# VIC-20_AV-Adaptor.net
KiCad netlist of a schematic drawn in EAGLE
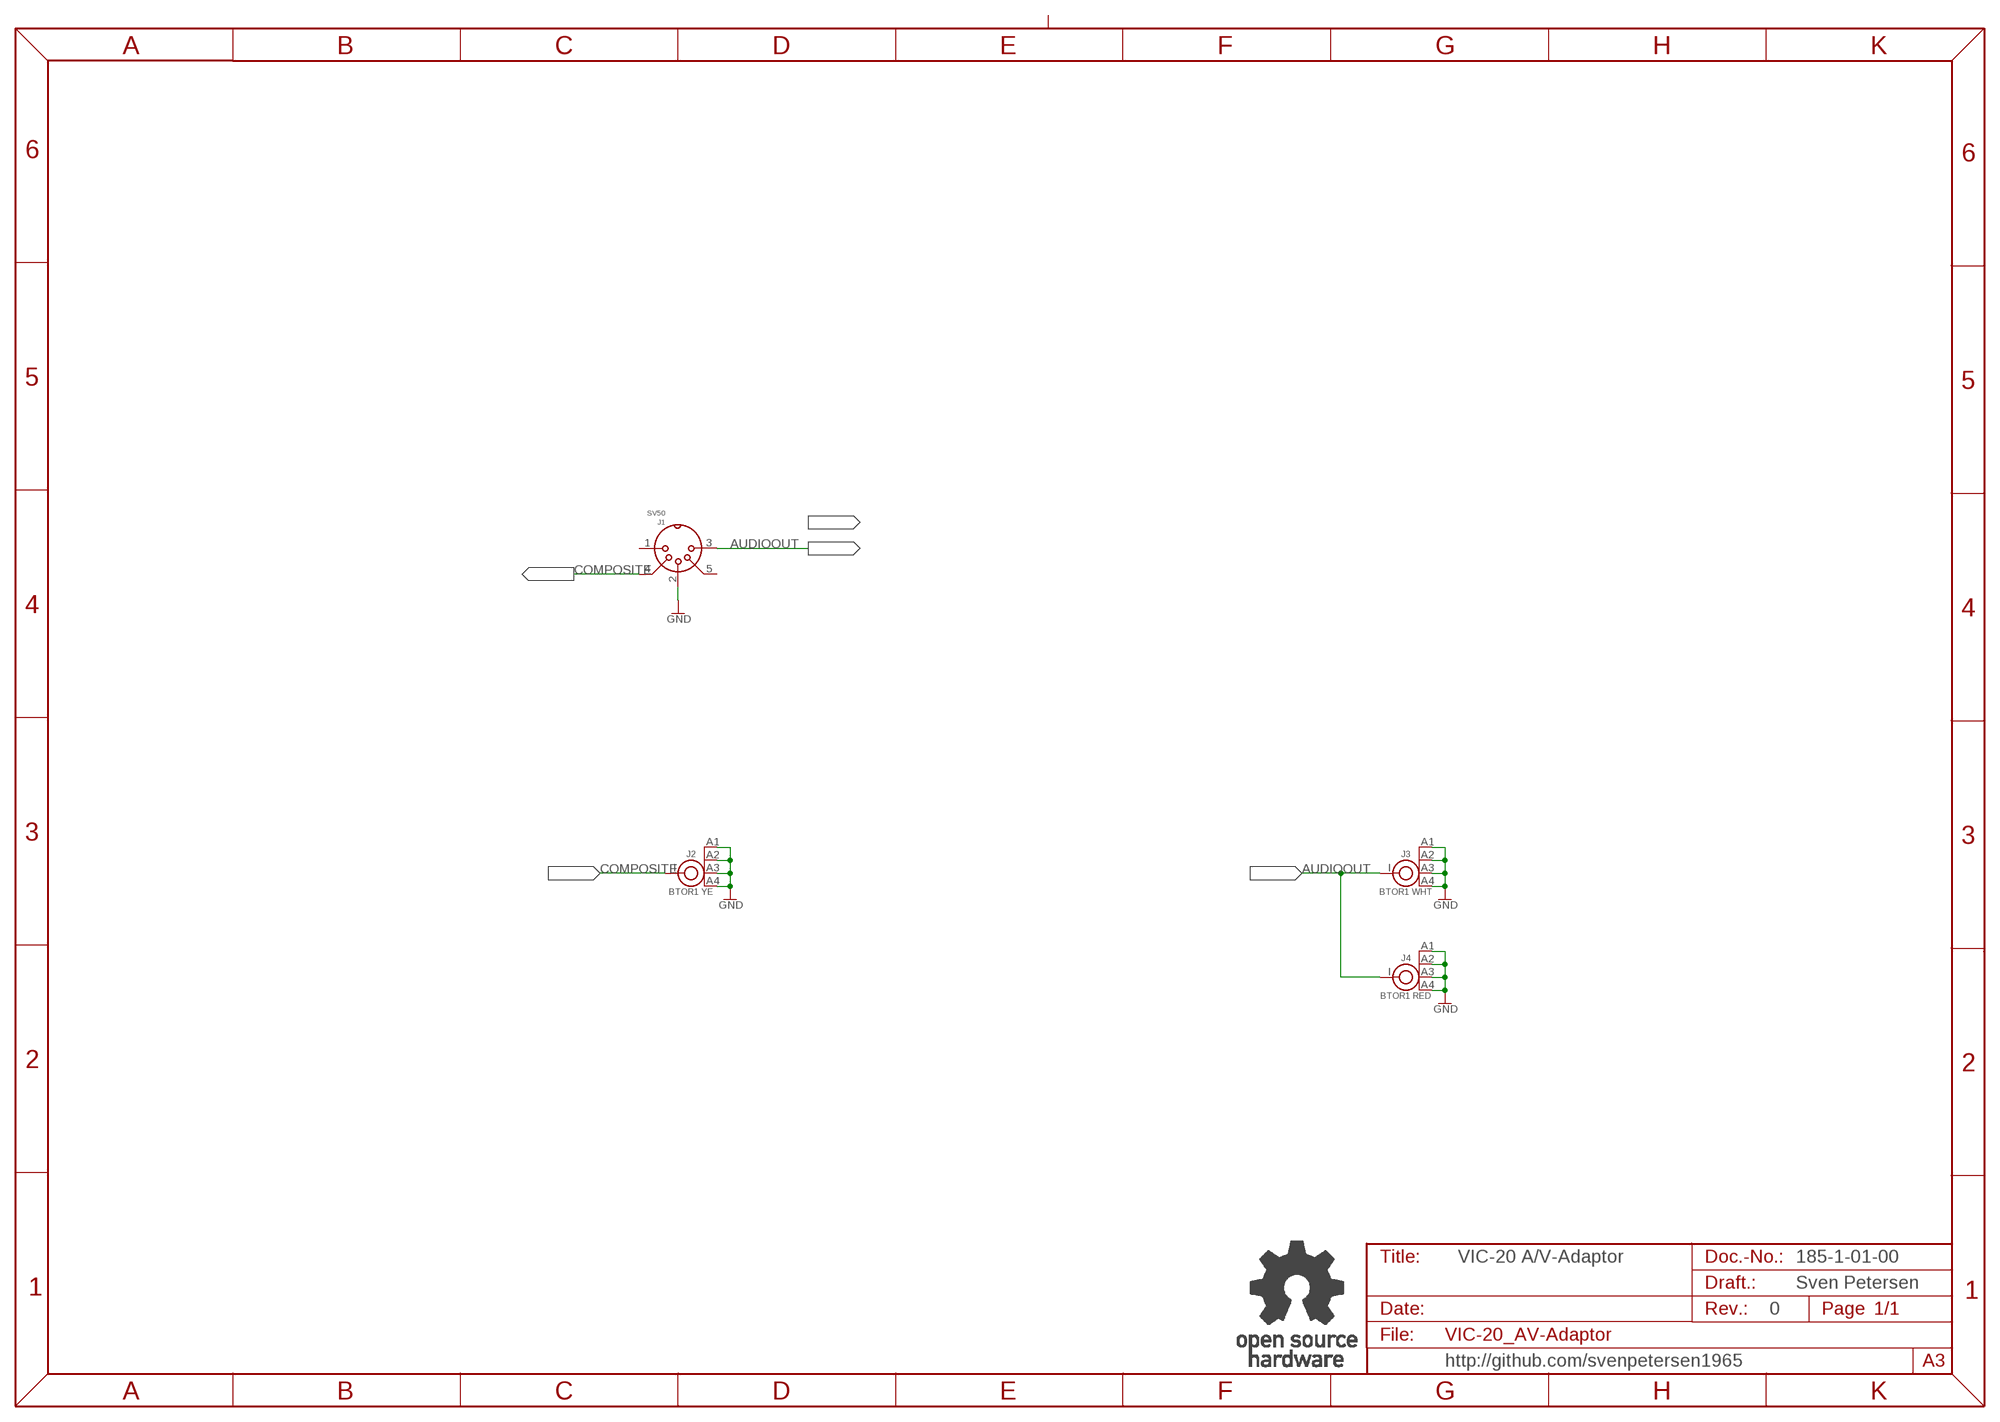
[diagram p0: schematic, sheet 1]

(export (version "E")
  (design (tool "Eeschema 10.0.6"))
  (components
    (comp (ref "J1")
      (value "SV50")
      (footprint "eagle-import:SV50_INNER")
      (libsource (lib "eagle-import") (part "SV50"))
    )
    (comp (ref "J2")
      (value "BTOR1 YE")
      (footprint "eagle-import:BTOR1")
      (libsource (lib "eagle-import") (part "BTOR1"))
    )
    (comp (ref "J3")
      (value "BTOR1 WHT")
      (footprint "eagle-import:BTOR1")
      (libsource (lib "eagle-import") (part "BTOR1"))
    )
    (comp (ref "J4")
      (value "BTOR1 RED")
      (footprint "eagle-import:BTOR1")
      (libsource (lib "eagle-import") (part "BTOR1"))
    )
    (comp (ref "U$25")
      (value "OPEN_SOURCE_HW")
      (footprint "eagle-import:OPENHW")
      (libsource (lib "eagle-import") (part "OPEN_SOURCE_HW"))
    )
  )
  (nets
    (net (code "1") (name "/AUDIOOUT") (class "Default")
      (node (ref "J1") (pin "3") (pinfunction "3_3") (pintype "bidirectional"))
      (node (ref "J3") (pin "I") (pinfunction "I_I") (pintype "bidirectional"))
      (node (ref "J4") (pin "I") (pinfunction "I_I") (pintype "bidirectional"))
    )
    (net (code "2") (name "/COMPOSITE") (class "Default")
      (node (ref "J1") (pin "4") (pinfunction "4_4") (pintype "bidirectional"))
      (node (ref "J2") (pin "I") (pinfunction "I_I") (pintype "bidirectional"))
    )
    (net (code "3") (name "GND") (class "Default")
      (node (ref "J1") (pin "2") (pinfunction "2_2") (pintype "bidirectional"))
      (node (ref "J2") (pin "A1") (pinfunction "A1_A1") (pintype "bidirectional"))
      (node (ref "J2") (pin "A2") (pinfunction "A2_A2") (pintype "bidirectional"))
      (node (ref "J2") (pin "A3") (pinfunction "A3_A3") (pintype "bidirectional"))
      (node (ref "J2") (pin "A4") (pinfunction "A4_A4") (pintype "bidirectional"))
      (node (ref "J3") (pin "A1") (pinfunction "A1_A1") (pintype "bidirectional"))
      (node (ref "J3") (pin "A2") (pinfunction "A2_A2") (pintype "bidirectional"))
      (node (ref "J3") (pin "A3") (pinfunction "A3_A3") (pintype "bidirectional"))
      (node (ref "J3") (pin "A4") (pinfunction "A4_A4") (pintype "bidirectional"))
      (node (ref "J4") (pin "A1") (pinfunction "A1_A1") (pintype "bidirectional"))
      (node (ref "J4") (pin "A2") (pinfunction "A2_A2") (pintype "bidirectional"))
      (node (ref "J4") (pin "A3") (pinfunction "A3_A3") (pintype "bidirectional"))
      (node (ref "J4") (pin "A4") (pinfunction "A4_A4") (pintype "bidirectional"))
    )
    (net (code "4") (name "unconnected-(J1-Pad1)") (class "Default")
      (node (ref "J1") (pin "1") (pinfunction "1_1") (pintype "bidirectional"))
    )
    (net (code "5") (name "unconnected-(J1-Pad5)") (class "Default")
      (node (ref "J1") (pin "5") (pinfunction "5_5") (pintype "bidirectional"))
    )
  )
)
